# Part24.net
KiCad netlist of a schematic drawn in Altium Designer
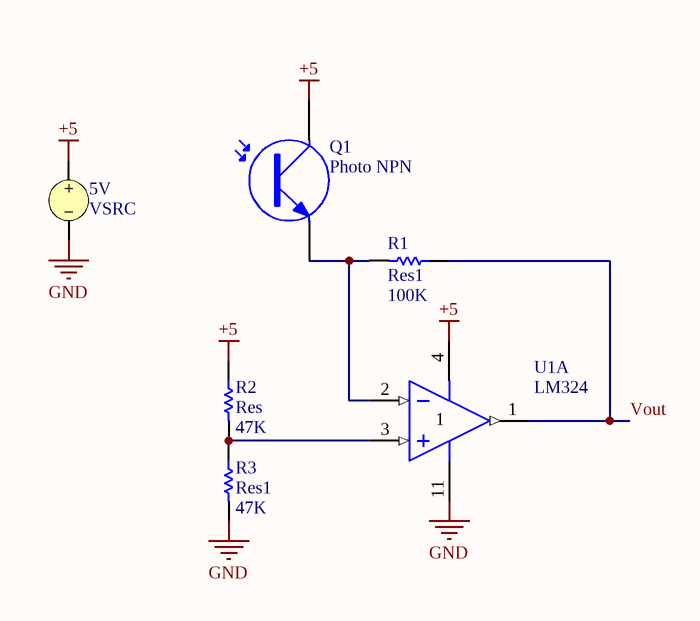
[diagram p0: Part24.SchDoc]

(export (version "E")
  (design (tool "Eeschema 10.0.6"))
  (components
    (comp (ref "5V")
      (value "VSRC")
      (description "Voltage Source")
      (fields (field (name "PUBLISHER") "Altium Limited"))
      (libsource (lib "Simulation Sources") (part "VSRC"))
    )
    (comp (ref "Q1")
      (value "Photo NPN")
      (footprint "SFM-T2(3)/X1.6V")
      (description "NPN Phototransistor")
      (fields (field (name "MANUFACTURER") "Generic Components"))
      (libsource (lib "ME218_BaseLib") (part "Photo NPN"))
    )
    (comp (ref "R1")
      (value "Res1")
      (footprint "AXIAL-0.3")
      (description "Resistor")
      (fields
        (field (name "MANUFACTURER") "Generic Components")
        (field (name "ALTIUM_VALUE") "100K")
        (field (name "PUBLISHER") "Altium Hobart Technology Centre")
      )
      (libsource (lib "ME218_BaseLib") (part "Res1"))
    )
    (comp (ref "R2")
      (value "Res")
      (footprint "AXIAL-0.3")
      (description "Resistor")
      (fields
        (field (name "MANUFACTURER") "Generic Components")
        (field (name "ALTIUM_VALUE") "47K")
        (field (name "PUBLISHER") "Altium Hobart Technology Centre")
      )
      (libsource (lib "ME218_BaseLib") (part "Res1"))
    )
    (comp (ref "R3")
      (value "Res1")
      (footprint "AXIAL-0.3")
      (description "Resistor")
      (fields
        (field (name "MANUFACTURER") "Generic Components")
        (field (name "ALTIUM_VALUE") "47K")
        (field (name "PUBLISHER") "Altium Hobart Technology Centre")
      )
      (libsource (lib "ME218_BaseLib") (part "Res1"))
    )
    (comp (ref "U1")
      (value "LM324")
      (footprint "DIP-14")
      (description "Low-Power Quad Operational Amplifier")
      (fields
        (field (name "MANUFACTURER") "National Semiconductor")
        (field (name "PUBLISHER") "Altium Hobart Technology Centre")
      )
      (libsource (lib "ME218_BaseLib") (part "LM324AJ"))
    )
  )
  (nets
    (net (code "1") (name "+5") (class "Default")
      (node (ref "5V") (pin "1") (pinfunction "1_1") (pintype "passive"))
      (node (ref "Q1") (pin "1") (pinfunction "C_1") (pintype "passive"))
      (node (ref "R2") (pin "1") (pinfunction "1_1") (pintype "passive"))
      (node (ref "U1") (pin "4") (pinfunction "V+_4") (pintype "power_in"))
    )
    (net (code "2") (name "/Vout") (class "Default")
      (node (ref "R1") (pin "1") (pinfunction "1_1") (pintype "passive"))
      (node (ref "U1") (pin "1") (pinfunction "OUT_1") (pintype "output"))
    )
    (net (code "3") (name "GND") (class "Default")
      (node (ref "5V") (pin "2") (pinfunction "2_2") (pintype "passive"))
      (node (ref "R3") (pin "2") (pinfunction "2_2") (pintype "passive"))
      (node (ref "U1") (pin "11") (pinfunction "GND_11") (pintype "power_in"))
    )
    (net (code "4") (name "Net-(Q1-E)") (class "Default")
      (node (ref "Q1") (pin "3") (pinfunction "E_3") (pintype "passive"))
      (node (ref "R1") (pin "2") (pinfunction "2_2") (pintype "passive"))
      (node (ref "U1") (pin "2") (pinfunction "IN-_2") (pintype "input"))
    )
    (net (code "5") (name "Net-(U1A-IN+)") (class "Default")
      (node (ref "R2") (pin "2") (pinfunction "2_2") (pintype "passive"))
      (node (ref "R3") (pin "1") (pinfunction "1_1") (pintype "passive"))
      (node (ref "U1") (pin "3") (pinfunction "IN+_3") (pintype "input"))
    )
  )
)
